# Quad_Schematic.net
KiCad netlist of a schematic drawn in EAGLE
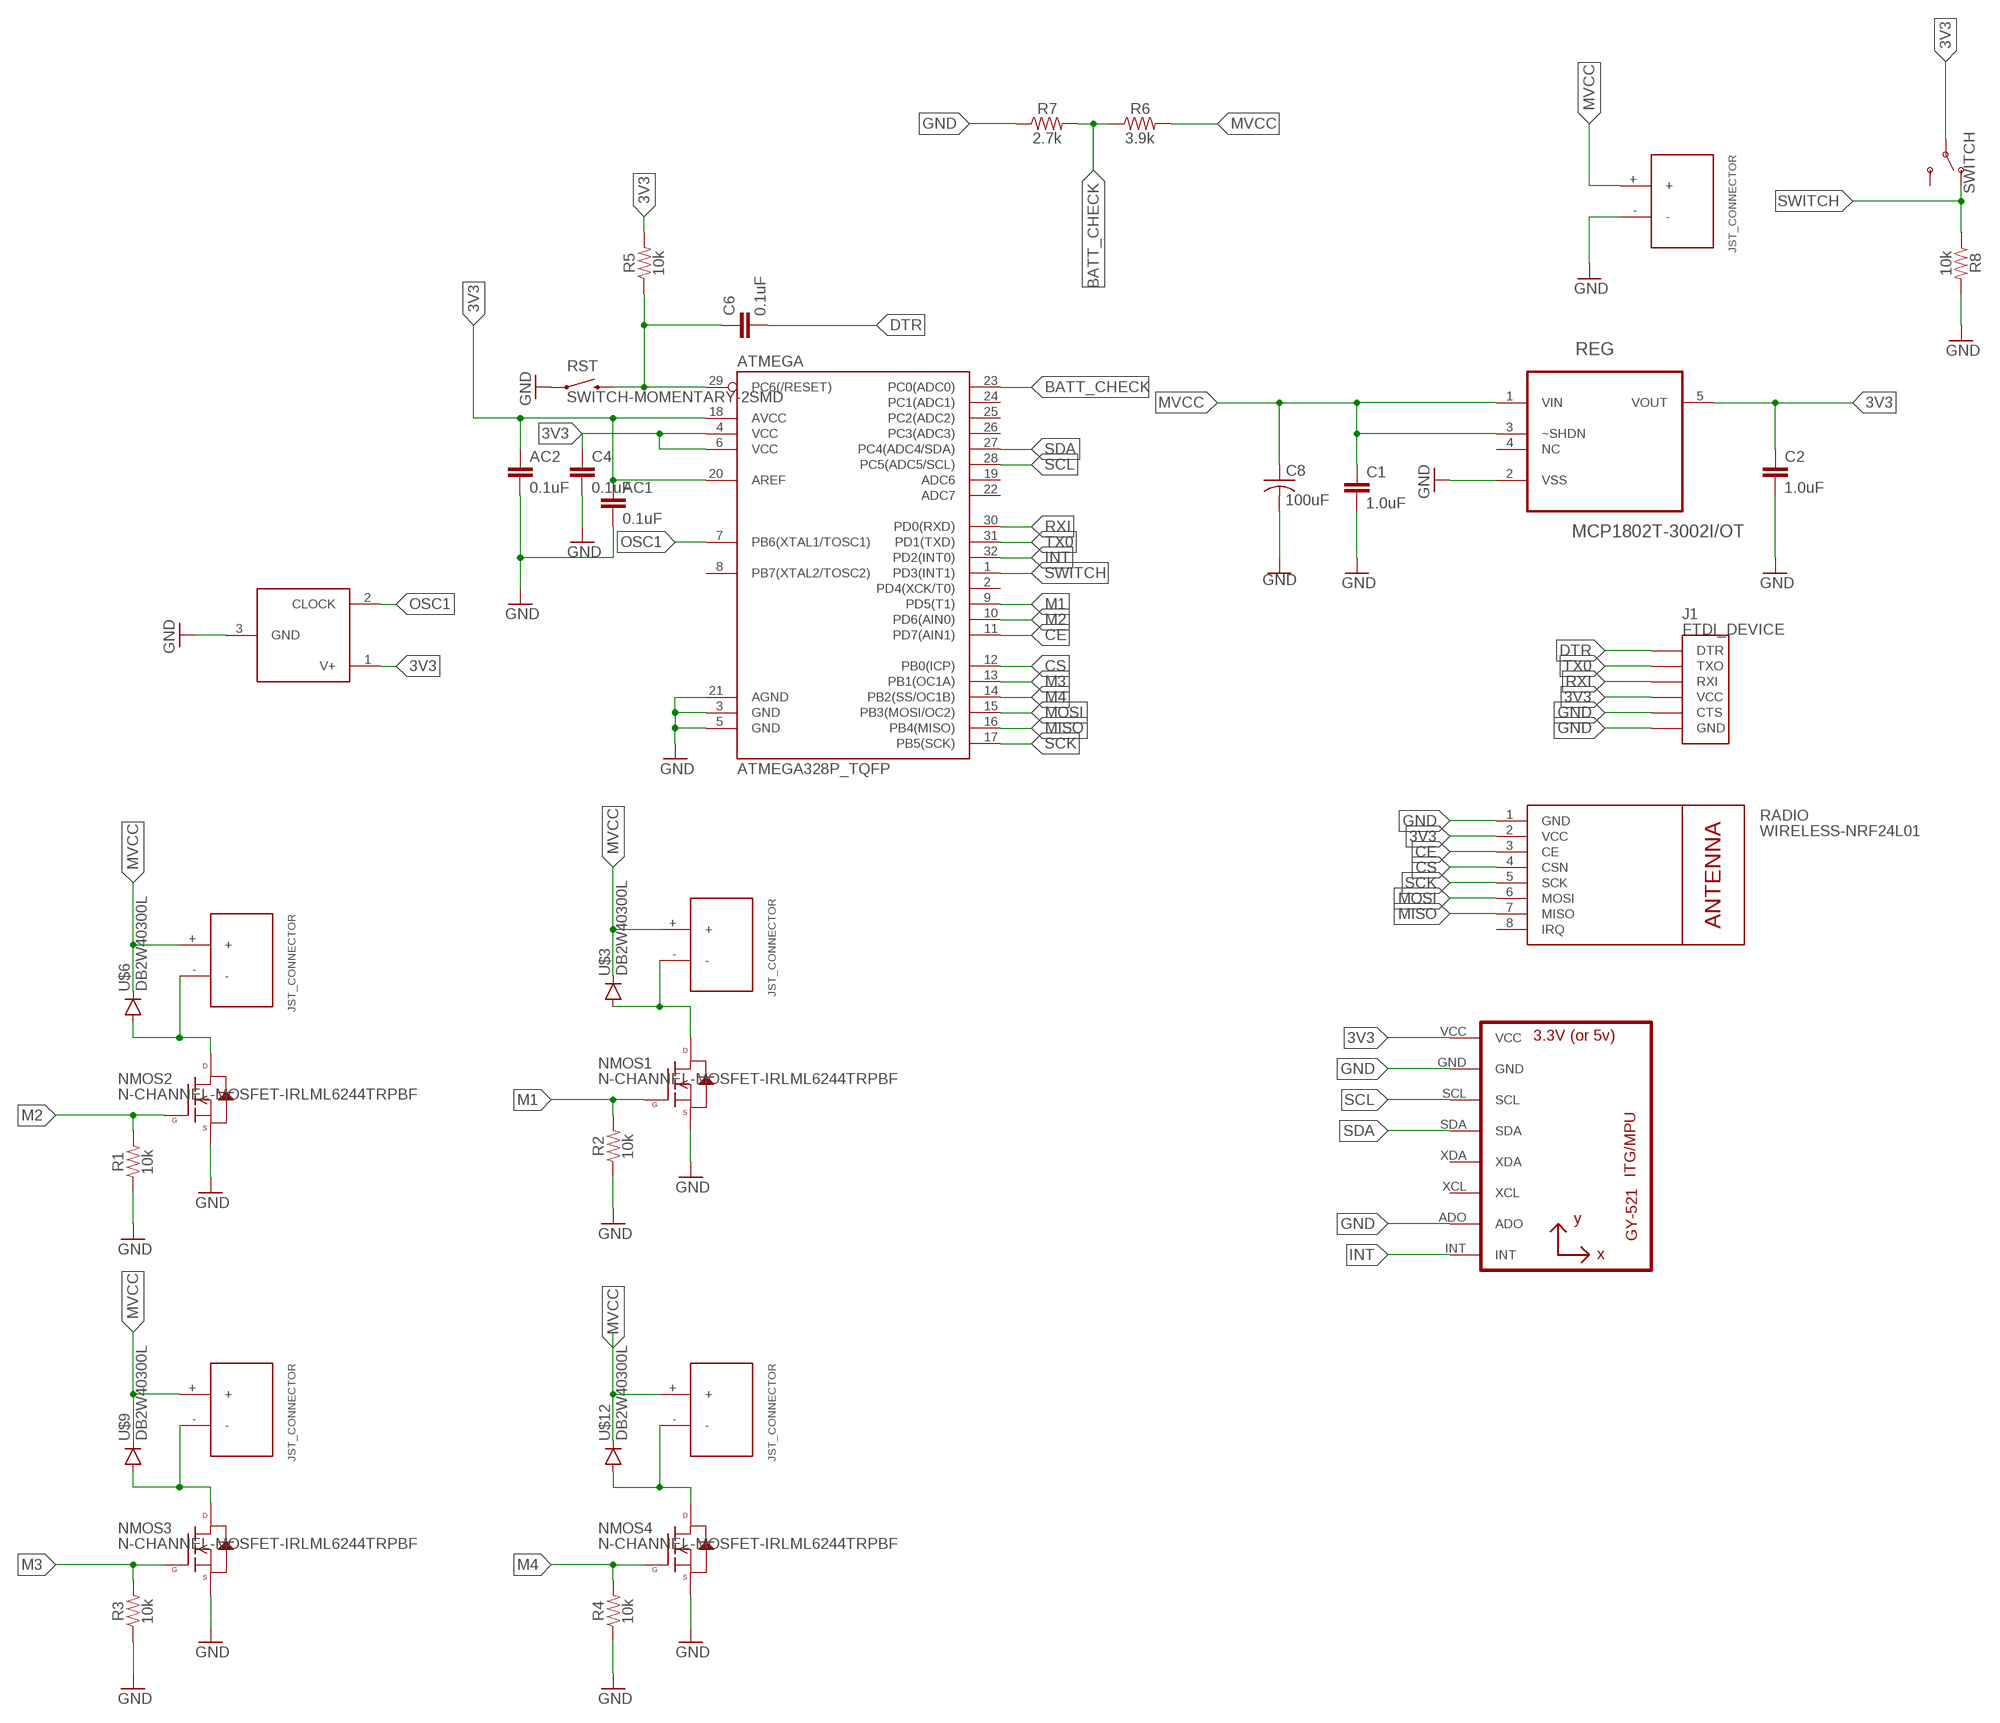
[diagram p0: schematic, sheet 1]

(export (version "E")
  (design (tool "Eeschema 10.0.6"))
  (components
    (comp (ref "AC1")
      (value "0.1uF")
      (footprint "eagle-import:0603")
      (libsource (lib "eagle-import") (part "0.1UF-0603-25V-5%"))
    )
    (comp (ref "AC2")
      (value "0.1uF")
      (footprint "eagle-import:0603")
      (libsource (lib "eagle-import") (part "0.1UF-0603-25V-5%"))
    )
    (comp (ref "ATMEGA")
      (value "ATMEGA328P_TQFP")
      (footprint "eagle-import:TQFP32-08")
      (libsource (lib "eagle-import") (part "ATMEGA328P_TQFP"))
    )
    (comp (ref "BATT")
      (value "JST_CONNECTOR_FEMALE")
      (footprint "eagle-import:JST_CONNECTOR_FEMALE")
      (libsource (lib "eagle-import") (part "JST_CONNECTOR_FEMALE"))
    )
    (comp (ref "C1")
      (value "1.0uF")
      (footprint "eagle-import:0603")
      (libsource (lib "eagle-import") (part "1.0UF-0603-16V-10%"))
    )
    (comp (ref "C2")
      (value "1.0uF")
      (footprint "eagle-import:0603")
      (libsource (lib "eagle-import") (part "1.0UF-0603-16V-10%"))
    )
    (comp (ref "C4")
      (value "0.1uF")
      (footprint "eagle-import:0603")
      (libsource (lib "eagle-import") (part "0.1UF-0603-25V-5%"))
    )
    (comp (ref "C6")
      (value "0.1uF")
      (footprint "eagle-import:0603")
      (libsource (lib "eagle-import") (part "0.1UF-0603-25V-5%"))
    )
    (comp (ref "C8")
      (value "100uF")
      (footprint "eagle-import:C1210")
      (libsource (lib "eagle-import") (part "C-USC1210"))
    )
    (comp (ref "J1")
      (value "FTDI_DEVICE")
      (footprint "eagle-import:FTDI_DEVICE_SIDE")
      (libsource (lib "eagle-import") (part "FTDI_DEVICE"))
    )
    (comp (ref "NMOS1")
      (value "N-CHANNEL-MOSFET-IRLML6244TRPBF")
      (footprint "eagle-import:SOT23-3")
      (libsource (lib "eagle-import") (part "N-CHANNEL-MOSFET-IRLML6244TRPBF"))
    )
    (comp (ref "NMOS2")
      (value "N-CHANNEL-MOSFET-IRLML6244TRPBF")
      (footprint "eagle-import:SOT23-3")
      (libsource (lib "eagle-import") (part "N-CHANNEL-MOSFET-IRLML6244TRPBF"))
    )
    (comp (ref "NMOS3")
      (value "N-CHANNEL-MOSFET-IRLML6244TRPBF")
      (footprint "eagle-import:SOT23-3")
      (libsource (lib "eagle-import") (part "N-CHANNEL-MOSFET-IRLML6244TRPBF"))
    )
    (comp (ref "NMOS4")
      (value "N-CHANNEL-MOSFET-IRLML6244TRPBF")
      (footprint "eagle-import:SOT23-3")
      (libsource (lib "eagle-import") (part "N-CHANNEL-MOSFET-IRLML6244TRPBF"))
    )
    (comp (ref "OSC")
      (value "MAX7375")
      (footprint "eagle-import:SC70-3L")
      (libsource (lib "eagle-import") (part "MAX7375"))
    )
    (comp (ref "R1")
      (value "10k")
      (footprint "eagle-import:0603")
      (libsource (lib "eagle-import") (part "10KOHM-0603-1/10W-1%"))
    )
    (comp (ref "R2")
      (value "10k")
      (footprint "eagle-import:0603")
      (libsource (lib "eagle-import") (part "10KOHM-0603-1/10W-1%"))
    )
    (comp (ref "R3")
      (value "10k")
      (footprint "eagle-import:0603")
      (libsource (lib "eagle-import") (part "10KOHM-0603-1/10W-1%"))
    )
    (comp (ref "R4")
      (value "10k")
      (footprint "eagle-import:0603")
      (libsource (lib "eagle-import") (part "10KOHM-0603-1/10W-1%"))
    )
    (comp (ref "R5")
      (value "10k")
      (footprint "eagle-import:0603")
      (libsource (lib "eagle-import") (part "10KOHM-0603-1/10W-1%"))
    )
    (comp (ref "R6")
      (value "3.9k")
      (footprint "eagle-import:0603")
      (libsource (lib "eagle-import") (part "6.8KOHM-0603-1/10W-1%"))
    )
    (comp (ref "R7")
      (value "2.7k")
      (footprint "eagle-import:0603")
      (libsource (lib "eagle-import") (part "5.6KOHM-0603-1/10W-1%"))
    )
    (comp (ref "R8")
      (value "10k")
      (footprint "eagle-import:0603")
      (libsource (lib "eagle-import") (part "10KOHM-0603-1/10W-1%"))
    )
    (comp (ref "RADIO")
      (value "WIRELESS-NRF24L01")
      (footprint "eagle-import:WIRELESS-NRF24L01")
      (libsource (lib "eagle-import") (part "WIRELESS-NRF24L01"))
    )
    (comp (ref "REG")
      (value "MCP1802T-3002I/OT")
      (footprint "eagle-import:SOT95P270X145-5N")
      (libsource (lib "eagle-import") (part "MCP1802T-3002I/OT"))
    )
    (comp (ref "RST")
      (value "SWITCH-MOMENTARY-2SMD")
      (footprint "eagle-import:TACTILE-SWITCH-SMD")
      (libsource (lib "eagle-import") (part "SWITCH-MOMENTARY-2SMD"))
    )
    (comp (ref "SWITCH")
      (value "SWITCH-SPDT-PTH-11.6X4.0MM")
      (footprint "eagle-import:SWITCH_SPDT_PTH_11.6X4.0MM")
      (libsource (lib "eagle-import") (part "SWITCH-SPDT-PTH-11.6X4.0MM"))
    )
    (comp (ref "U$2")
      (value "JST_CONNECTOR_FEMALE")
      (footprint "eagle-import:JST_CONNECTOR_FEMALE")
      (libsource (lib "eagle-import") (part "JST_CONNECTOR_FEMALE"))
    )
    (comp (ref "U$3")
      (value "DB2W40300L")
      (footprint "eagle-import:MINI2-F3-B")
      (libsource (lib "eagle-import") (part "DB2W40300L"))
    )
    (comp (ref "U$5")
      (value "JST_CONNECTOR_FEMALE")
      (footprint "eagle-import:JST_CONNECTOR_FEMALE")
      (libsource (lib "eagle-import") (part "JST_CONNECTOR_FEMALE"))
    )
    (comp (ref "U$6")
      (value "DB2W40300L")
      (footprint "eagle-import:MINI2-F3-B")
      (libsource (lib "eagle-import") (part "DB2W40300L"))
    )
    (comp (ref "U$8")
      (value "JST_CONNECTOR_FEMALE")
      (footprint "eagle-import:JST_CONNECTOR_FEMALE")
      (libsource (lib "eagle-import") (part "JST_CONNECTOR_FEMALE"))
    )
    (comp (ref "U$9")
      (value "DB2W40300L")
      (footprint "eagle-import:MINI2-F3-B")
      (libsource (lib "eagle-import") (part "DB2W40300L"))
    )
    (comp (ref "U$11")
      (value "JST_CONNECTOR_FEMALE")
      (footprint "eagle-import:JST_CONNECTOR_FEMALE")
      (libsource (lib "eagle-import") (part "JST_CONNECTOR_FEMALE"))
    )
    (comp (ref "U$12")
      (value "DB2W40300L")
      (footprint "eagle-import:MINI2-F3-B")
      (libsource (lib "eagle-import") (part "DB2W40300L"))
    )
    (comp (ref "U2")
      (value "GY-521MPU6050")
      (footprint "eagle-import:GY-521")
      (libsource (lib "eagle-import") (part "GY-521MPU6050"))
    )
  )
  (nets
    (net (code "1") (name "3V3") (class "Default")
      (node (ref "AC1") (pin "1") (pinfunction "1_1") (pintype "passive"))
      (node (ref "AC2") (pin "1") (pinfunction "1_1") (pintype "passive"))
      (node (ref "ATMEGA") (pin "18") (pinfunction "AVCC_18") (pintype "bidirectional"))
      (node (ref "ATMEGA") (pin "20") (pinfunction "AREF_20") (pintype "bidirectional"))
      (node (ref "ATMEGA") (pin "4") (pinfunction "VCC_4") (pintype "bidirectional"))
      (node (ref "ATMEGA") (pin "6") (pinfunction "VCC_6") (pintype "bidirectional"))
      (node (ref "C2") (pin "1") (pinfunction "1_1") (pintype "passive"))
      (node (ref "C4") (pin "1") (pinfunction "1_1") (pintype "passive"))
      (node (ref "J1") (pin "P$4") (pinfunction "VCC_P$4") (pintype "bidirectional"))
      (node (ref "OSC") (pin "1") (pinfunction "V+_1") (pintype "bidirectional"))
      (node (ref "R5") (pin "2") (pinfunction "2_2") (pintype "passive"))
      (node (ref "RADIO") (pin "2") (pinfunction "VCC_2") (pintype "power_in"))
      (node (ref "REG") (pin "5") (pinfunction "VOUT_5") (pintype "output"))
      (node (ref "SWITCH") (pin "2") (pinfunction "P_2") (pintype "passive"))
      (node (ref "U2") (pin "VCC") (pinfunction "VCC_VCC") (pintype "bidirectional"))
    )
    (net (code "2") (name "BATT_CHECK") (class "Default")
      (node (ref "ATMEGA") (pin "23") (pinfunction "PC0(ADC0)_23") (pintype "bidirectional"))
      (node (ref "R6") (pin "1") (pinfunction "1_1") (pintype "passive"))
      (node (ref "R7") (pin "2") (pinfunction "2_2") (pintype "passive"))
    )
    (net (code "3") (name "CE") (class "Default")
      (node (ref "ATMEGA") (pin "11") (pinfunction "PD7(AIN1)_11") (pintype "bidirectional"))
      (node (ref "RADIO") (pin "3") (pinfunction "CE_3") (pintype "bidirectional"))
    )
    (net (code "4") (name "CS") (class "Default")
      (node (ref "ATMEGA") (pin "12") (pinfunction "PB0(ICP)_12") (pintype "bidirectional"))
      (node (ref "RADIO") (pin "4") (pinfunction "CSN_4") (pintype "bidirectional"))
    )
    (net (code "5") (name "DTR") (class "Default")
      (node (ref "C6") (pin "2") (pinfunction "2_2") (pintype "passive"))
      (node (ref "J1") (pin "P$1") (pinfunction "DTR_P$1") (pintype "bidirectional"))
    )
    (net (code "6") (name "GND") (class "Default")
      (node (ref "AC1") (pin "2") (pinfunction "2_2") (pintype "passive"))
      (node (ref "AC2") (pin "2") (pinfunction "2_2") (pintype "passive"))
      (node (ref "ATMEGA") (pin "21") (pinfunction "AGND_21") (pintype "bidirectional"))
      (node (ref "ATMEGA") (pin "3") (pinfunction "GND_3") (pintype "bidirectional"))
      (node (ref "ATMEGA") (pin "5") (pinfunction "GND_5") (pintype "bidirectional"))
      (node (ref "BATT") (pin "-") (pinfunction "-_-") (pintype "bidirectional"))
      (node (ref "C1") (pin "2") (pinfunction "2_2") (pintype "passive"))
      (node (ref "C2") (pin "2") (pinfunction "2_2") (pintype "passive"))
      (node (ref "C4") (pin "2") (pinfunction "2_2") (pintype "passive"))
      (node (ref "C8") (pin "2") (pinfunction "2_2") (pintype "passive"))
      (node (ref "J1") (pin "P$5") (pinfunction "CTS_P$5") (pintype "bidirectional"))
      (node (ref "J1") (pin "P$6") (pinfunction "GND_P$6") (pintype "bidirectional"))
      (node (ref "NMOS1") (pin "2") (pinfunction "S_2") (pintype "passive"))
      (node (ref "NMOS2") (pin "2") (pinfunction "S_2") (pintype "passive"))
      (node (ref "NMOS3") (pin "2") (pinfunction "S_2") (pintype "passive"))
      (node (ref "NMOS4") (pin "2") (pinfunction "S_2") (pintype "passive"))
      (node (ref "OSC") (pin "3") (pinfunction "GND_3") (pintype "bidirectional"))
      (node (ref "R1") (pin "1") (pinfunction "1_1") (pintype "passive"))
      (node (ref "R2") (pin "1") (pinfunction "1_1") (pintype "passive"))
      (node (ref "R3") (pin "1") (pinfunction "1_1") (pintype "passive"))
      (node (ref "R4") (pin "1") (pinfunction "1_1") (pintype "passive"))
      (node (ref "R7") (pin "1") (pinfunction "1_1") (pintype "passive"))
      (node (ref "R8") (pin "2") (pinfunction "2_2") (pintype "passive"))
      (node (ref "RADIO") (pin "1") (pinfunction "GND_1") (pintype "power_in"))
      (node (ref "REG") (pin "2") (pinfunction "VSS_2") (pintype "passive"))
      (node (ref "RST") (pin "1") (pinfunction "1_1") (pintype "passive"))
      (node (ref "U2") (pin "ADO") (pinfunction "ADO_ADO") (pintype "bidirectional"))
      (node (ref "U2") (pin "GND") (pinfunction "GND_GND") (pintype "bidirectional"))
    )
    (net (code "7") (name "INT") (class "Default")
      (node (ref "ATMEGA") (pin "32") (pinfunction "PD2(INT0)_32") (pintype "bidirectional"))
      (node (ref "U2") (pin "INT") (pinfunction "INT_INT") (pintype "bidirectional"))
    )
    (net (code "8") (name "M1") (class "Default")
      (node (ref "ATMEGA") (pin "9") (pinfunction "PD5(T1)_9") (pintype "bidirectional"))
      (node (ref "NMOS1") (pin "1") (pinfunction "G_1") (pintype "passive"))
      (node (ref "R2") (pin "2") (pinfunction "2_2") (pintype "passive"))
    )
    (net (code "9") (name "M2") (class "Default")
      (node (ref "ATMEGA") (pin "10") (pinfunction "PD6(AIN0)_10") (pintype "bidirectional"))
      (node (ref "NMOS2") (pin "1") (pinfunction "G_1") (pintype "passive"))
      (node (ref "R1") (pin "2") (pinfunction "2_2") (pintype "passive"))
    )
    (net (code "10") (name "M3") (class "Default")
      (node (ref "ATMEGA") (pin "13") (pinfunction "PB1(OC1A)_13") (pintype "bidirectional"))
      (node (ref "NMOS3") (pin "1") (pinfunction "G_1") (pintype "passive"))
      (node (ref "R3") (pin "2") (pinfunction "2_2") (pintype "passive"))
    )
    (net (code "11") (name "M4") (class "Default")
      (node (ref "ATMEGA") (pin "14") (pinfunction "PB2(SS/OC1B)_14") (pintype "bidirectional"))
      (node (ref "NMOS4") (pin "1") (pinfunction "G_1") (pintype "passive"))
      (node (ref "R4") (pin "2") (pinfunction "2_2") (pintype "passive"))
    )
    (net (code "12") (name "MISO") (class "Default")
      (node (ref "ATMEGA") (pin "16") (pinfunction "PB4(MISO)_16") (pintype "bidirectional"))
      (node (ref "RADIO") (pin "7") (pinfunction "MISO_7") (pintype "bidirectional"))
    )
    (net (code "13") (name "MOSI") (class "Default")
      (node (ref "ATMEGA") (pin "15") (pinfunction "PB3(MOSI/OC2)_15") (pintype "bidirectional"))
      (node (ref "RADIO") (pin "6") (pinfunction "MOSI_6") (pintype "bidirectional"))
    )
    (net (code "14") (name "MVCC") (class "Default")
      (node (ref "BATT") (pin "+") (pinfunction "+_+") (pintype "bidirectional"))
      (node (ref "C1") (pin "1") (pinfunction "1_1") (pintype "passive"))
      (node (ref "C8") (pin "1") (pinfunction "1_1") (pintype "passive"))
      (node (ref "R6") (pin "2") (pinfunction "2_2") (pintype "passive"))
      (node (ref "REG") (pin "1") (pinfunction "VIN_1") (pintype "power_in"))
      (node (ref "REG") (pin "3") (pinfunction "~{SHDN}_3") (pintype "input"))
      (node (ref "U$11") (pin "+") (pinfunction "+_+") (pintype "bidirectional"))
      (node (ref "U$12") (pin "NEG") (pinfunction "GPIN_NEG") (pintype "passive"))
      (node (ref "U$2") (pin "+") (pinfunction "+_+") (pintype "bidirectional"))
      (node (ref "U$3") (pin "NEG") (pinfunction "GPIN_NEG") (pintype "passive"))
      (node (ref "U$5") (pin "+") (pinfunction "+_+") (pintype "bidirectional"))
      (node (ref "U$6") (pin "NEG") (pinfunction "GPIN_NEG") (pintype "passive"))
      (node (ref "U$8") (pin "+") (pinfunction "+_+") (pintype "bidirectional"))
      (node (ref "U$9") (pin "NEG") (pinfunction "GPIN_NEG") (pintype "passive"))
    )
    (net (code "15") (name "Net-(ATMEGA-PC6({slash}RESET))") (class "Default")
      (node (ref "ATMEGA") (pin "29") (pinfunction "PC6(/RESET)_29") (pintype "bidirectional"))
      (node (ref "C6") (pin "1") (pinfunction "1_1") (pintype "passive"))
      (node (ref "R5") (pin "1") (pinfunction "1_1") (pintype "passive"))
      (node (ref "RST") (pin "3") (pinfunction "2_3") (pintype "passive"))
    )
    (net (code "16") (name "Net-(NMOS1-D)") (class "Default")
      (node (ref "NMOS1") (pin "3") (pinfunction "D_3") (pintype "passive"))
      (node (ref "U$2") (pin "-") (pinfunction "-_-") (pintype "bidirectional"))
      (node (ref "U$3") (pin "POS") (pinfunction "PPIN_POS") (pintype "passive"))
    )
    (net (code "17") (name "Net-(NMOS2-D)") (class "Default")
      (node (ref "NMOS2") (pin "3") (pinfunction "D_3") (pintype "passive"))
      (node (ref "U$5") (pin "-") (pinfunction "-_-") (pintype "bidirectional"))
      (node (ref "U$6") (pin "POS") (pinfunction "PPIN_POS") (pintype "passive"))
    )
    (net (code "18") (name "Net-(NMOS3-D)") (class "Default")
      (node (ref "NMOS3") (pin "3") (pinfunction "D_3") (pintype "passive"))
      (node (ref "U$8") (pin "-") (pinfunction "-_-") (pintype "bidirectional"))
      (node (ref "U$9") (pin "POS") (pinfunction "PPIN_POS") (pintype "passive"))
    )
    (net (code "19") (name "Net-(NMOS4-D)") (class "Default")
      (node (ref "NMOS4") (pin "3") (pinfunction "D_3") (pintype "passive"))
      (node (ref "U$11") (pin "-") (pinfunction "-_-") (pintype "bidirectional"))
      (node (ref "U$12") (pin "POS") (pinfunction "PPIN_POS") (pintype "passive"))
    )
    (net (code "20") (name "OSC1") (class "Default")
      (node (ref "ATMEGA") (pin "7") (pinfunction "PB6(XTAL1/TOSC1)_7") (pintype "bidirectional"))
      (node (ref "OSC") (pin "2") (pinfunction "CLOCK_2") (pintype "bidirectional"))
    )
    (net (code "21") (name "RXI") (class "Default")
      (node (ref "ATMEGA") (pin "30") (pinfunction "PD0(RXD)_30") (pintype "bidirectional"))
      (node (ref "J1") (pin "P$3") (pinfunction "RXI_P$3") (pintype "bidirectional"))
    )
    (net (code "22") (name "SCK") (class "Default")
      (node (ref "ATMEGA") (pin "17") (pinfunction "PB5(SCK)_17") (pintype "bidirectional"))
      (node (ref "RADIO") (pin "5") (pinfunction "SCK_5") (pintype "bidirectional"))
    )
    (net (code "23") (name "SCL") (class "Default")
      (node (ref "ATMEGA") (pin "28") (pinfunction "PC5(ADC5/SCL)_28") (pintype "bidirectional"))
      (node (ref "U2") (pin "SCL") (pinfunction "SCL_SCL") (pintype "bidirectional"))
    )
    (net (code "24") (name "SDA") (class "Default")
      (node (ref "ATMEGA") (pin "27") (pinfunction "PC4(ADC4/SDA)_27") (pintype "bidirectional"))
      (node (ref "U2") (pin "SDA") (pinfunction "SDA_SDA") (pintype "bidirectional"))
    )
    (net (code "25") (name "SWITCH") (class "Default")
      (node (ref "ATMEGA") (pin "1") (pinfunction "PD3(INT1)_1") (pintype "bidirectional"))
      (node (ref "R8") (pin "1") (pinfunction "1_1") (pintype "passive"))
      (node (ref "SWITCH") (pin "1") (pinfunction "O_1") (pintype "passive"))
    )
    (net (code "26") (name "TX0") (class "Default")
      (node (ref "ATMEGA") (pin "31") (pinfunction "PD1(TXD)_31") (pintype "bidirectional"))
      (node (ref "J1") (pin "P$2") (pinfunction "TXO_P$2") (pintype "bidirectional"))
    )
    (net (code "27") (name "unconnected-(ATMEGA-ADC6-Pad19)") (class "Default")
      (node (ref "ATMEGA") (pin "19") (pinfunction "ADC6_19") (pintype "bidirectional"))
    )
    (net (code "28") (name "unconnected-(ATMEGA-ADC7-Pad22)") (class "Default")
      (node (ref "ATMEGA") (pin "22") (pinfunction "ADC7_22") (pintype "bidirectional"))
    )
    (net (code "29") (name "unconnected-(ATMEGA-PB7(XTAL2{slash}TOSC2)-Pad8)") (class "Default")
      (node (ref "ATMEGA") (pin "8") (pinfunction "PB7(XTAL2/TOSC2)_8") (pintype "bidirectional"))
    )
    (net (code "30") (name "unconnected-(ATMEGA-PC1(ADC1)-Pad24)") (class "Default")
      (node (ref "ATMEGA") (pin "24") (pinfunction "PC1(ADC1)_24") (pintype "bidirectional"))
    )
    (net (code "31") (name "unconnected-(ATMEGA-PC2(ADC2)-Pad25)") (class "Default")
      (node (ref "ATMEGA") (pin "25") (pinfunction "PC2(ADC2)_25") (pintype "bidirectional"))
    )
    (net (code "32") (name "unconnected-(ATMEGA-PC3(ADC3)-Pad26)") (class "Default")
      (node (ref "ATMEGA") (pin "26") (pinfunction "PC3(ADC3)_26") (pintype "bidirectional"))
    )
    (net (code "33") (name "unconnected-(ATMEGA-PD4(XCK{slash}T0)-Pad2)") (class "Default")
      (node (ref "ATMEGA") (pin "2") (pinfunction "PD4(XCK/T0)_2") (pintype "bidirectional"))
    )
    (net (code "34") (name "unconnected-(RADIO-IRQ-Pad8)") (class "Default")
      (node (ref "RADIO") (pin "8") (pinfunction "IRQ_8") (pintype "bidirectional"))
    )
    (net (code "35") (name "unconnected-(REG-NC-Pad4)") (class "Default")
      (node (ref "REG") (pin "4") (pinfunction "NC_4") (pintype "no_connect"))
    )
    (net (code "36") (name "unconnected-(SWITCH-S-Pad3)") (class "Default")
      (node (ref "SWITCH") (pin "3") (pinfunction "S_3") (pintype "passive"))
    )
    (net (code "37") (name "unconnected-(U2-PadXCL)") (class "Default")
      (node (ref "U2") (pin "XCL") (pinfunction "XCL_XCL") (pintype "bidirectional"))
    )
    (net (code "38") (name "unconnected-(U2-PadXDA)") (class "Default")
      (node (ref "U2") (pin "XDA") (pinfunction "XDA_XDA") (pintype "bidirectional"))
    )
  )
)
